# ultra-violet-tooth-sensor-mk-1_0.net
KiCad netlist of a schematic drawn in EAGLE
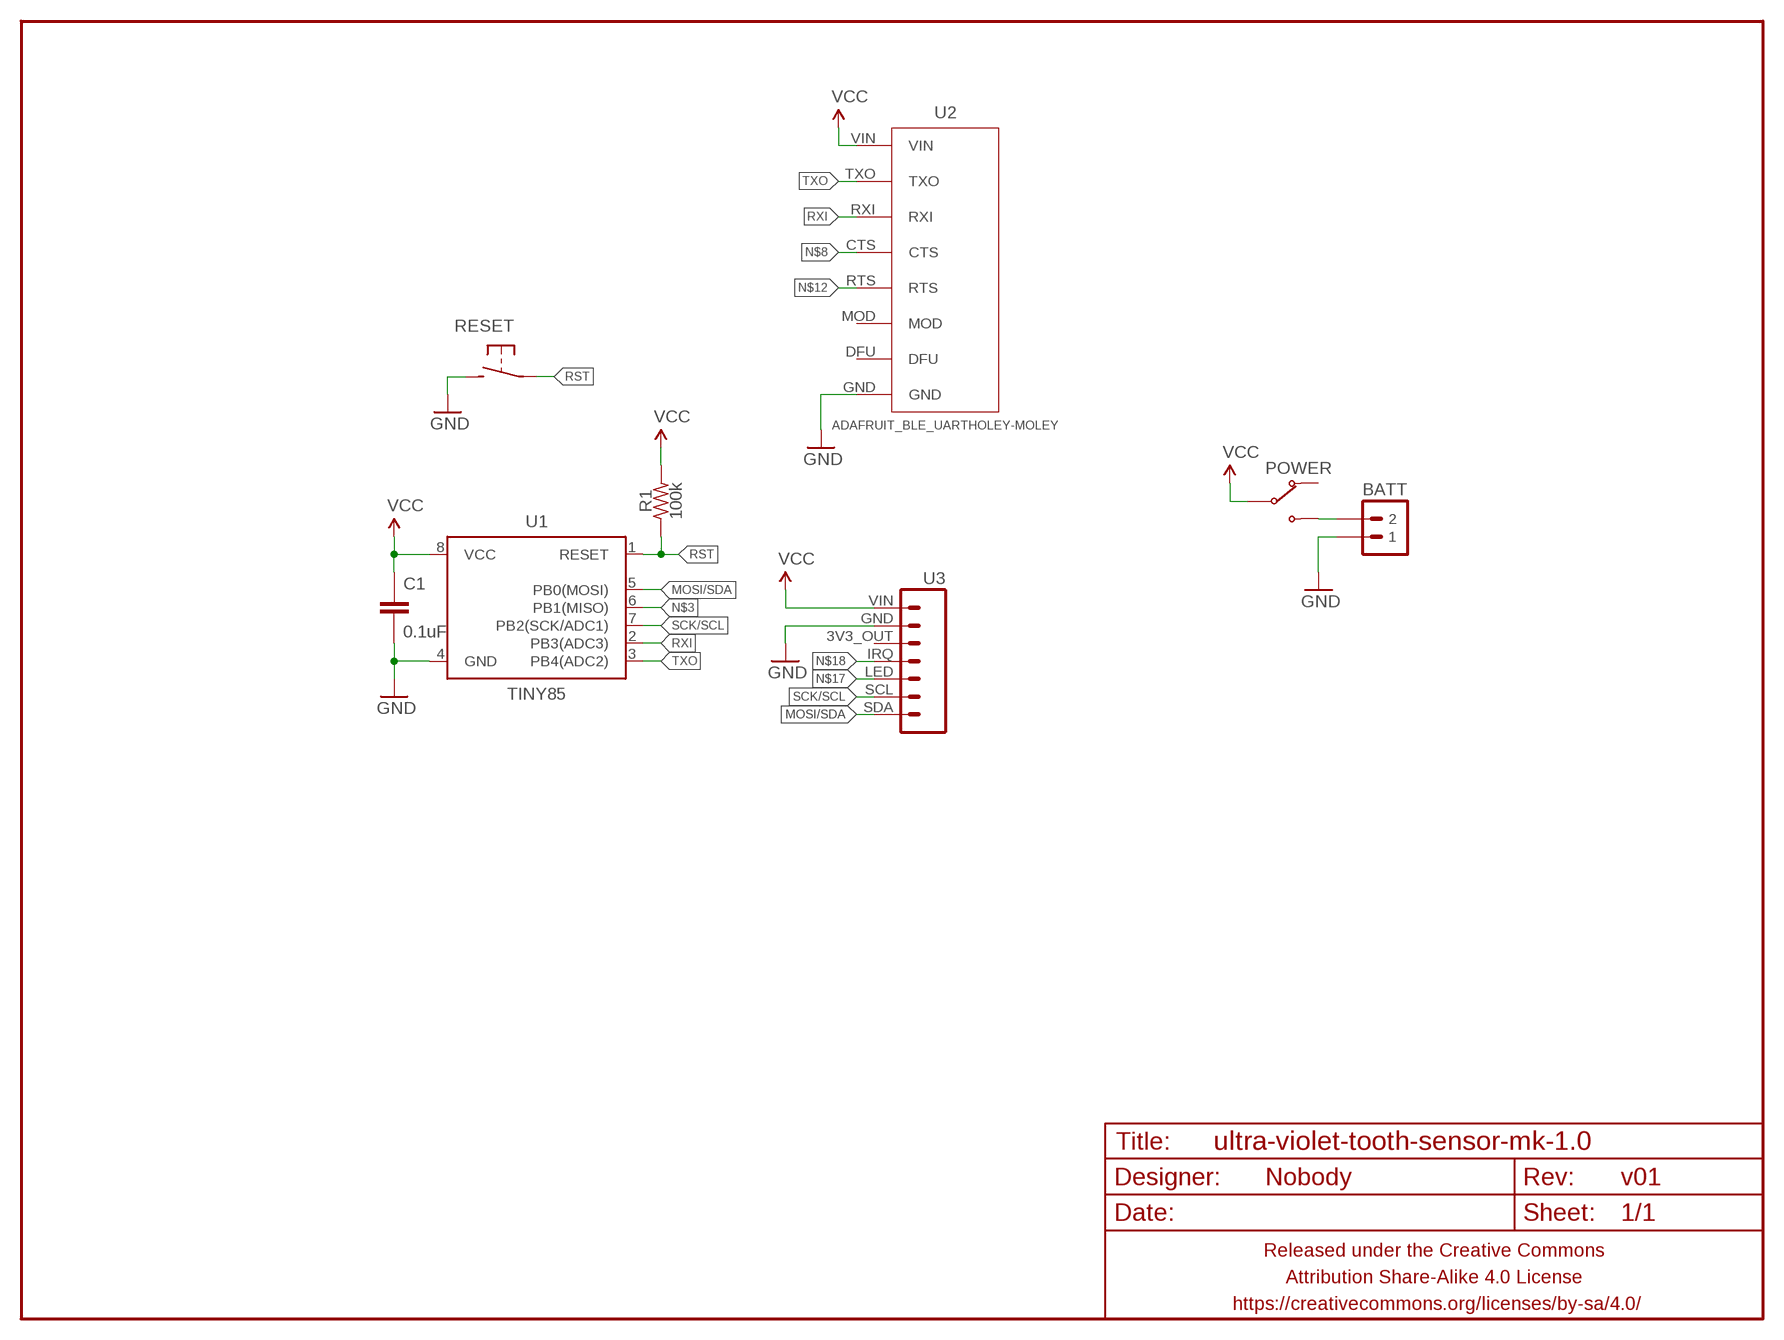
[diagram p0: schematic, sheet 1]

(export (version "E")
  (design (tool "Eeschema 10.0.6"))
  (components
    (comp (ref "BATT")
      (value "M02PTH-CENTERED-R+")
      (footprint "eagle-import:1X02-CENTER-R+")
      (libsource (lib "eagle-import") (part "M02PTH-CENTERED-R+"))
    )
    (comp (ref "C1")
      (value "0.1uF")
      (footprint "eagle-import:C025-024X044")
      (libsource (lib "eagle-import") (part "CAPACITOR-CERAMIC025-024X044"))
    )
    (comp (ref "FRAME1")
      (value "FRAME-LETTERNO_PACKAGE")
      (footprint "eagle-import:DUMMY")
      (fields (field (name "DESIGNER") "Nobody"))
      (libsource (lib "eagle-import") (part "FRAME-LETTERNO_PACKAGE"))
    )
    (comp (ref "POWER")
      (value "SWITCH-SPDTPTH-RA-2.54MM")
      (footprint "eagle-import:SPDT-RA-2.54MM")
      (libsource (lib "eagle-import") (part "SWITCH-SPDTPTH-RA-2.54MM"))
    )
    (comp (ref "R1")
      (value "100k")
      (footprint "eagle-import:RESISTOR-AXIAL-PTH-7.62MM")
      (libsource (lib "eagle-import") (part "RESISTORPTH-AXIAL-7.62MM"))
    )
    (comp (ref "RESET")
      (value "SPST-NO-TACT3MM-RA")
      (footprint "eagle-import:TACTILE-PTH-SIDE")
      (libsource (lib "eagle-import") (part "SPST-NO-TACT3MM-RA"))
    )
    (comp (ref "U1")
      (value "TINY85")
      (footprint "eagle-import:DIP08")
      (libsource (lib "eagle-import") (part "ATTINY45TINY85-20-DIP"))
    )
    (comp (ref "U2")
      (value "ADAFRUIT_BLE_UARTHOLEY-MOLEY")
      (footprint "eagle-import:ADAFRUIT_BLE_UART_HOLEY")
      (libsource (lib "eagle-import") (part "ADAFRUIT_BLE_UARTHOLEY-MOLEY"))
    )
    (comp (ref "U3")
      (value "ADAFRUIT-SI1145-BREAKOUT")
      (footprint "eagle-import:ADAFRUIT-SI1145-BREAKOUT")
      (libsource (lib "eagle-import") (part "ADAFRUIT-SI1145-BREAKOUT"))
    )
  )
  (nets
    (net (code "1") (name "GND") (class "Default")
      (node (ref "BATT") (pin "1") (pinfunction "1_1") (pintype "passive"))
      (node (ref "C1") (pin "2") (pinfunction "2_2") (pintype "passive"))
      (node (ref "RESET") (pin "2") (pinfunction "2_2") (pintype "passive"))
      (node (ref "U1") (pin "4") (pinfunction "GND_4") (pintype "bidirectional"))
      (node (ref "U2") (pin "GND") (pinfunction "GND_GND") (pintype "bidirectional"))
      (node (ref "U3") (pin "GND") (pinfunction "GND_GND") (pintype "passive"))
    )
    (net (code "2") (name "MOSI{slash}SDA") (class "Default")
      (node (ref "U1") (pin "5") (pinfunction "PB0(MOSI)_5") (pintype "bidirectional"))
      (node (ref "U3") (pin "SDA") (pinfunction "SDA_SDA") (pintype "passive"))
    )
    (net (code "3") (name "N$3") (class "Default")
      (node (ref "U1") (pin "6") (pinfunction "PB1(MISO)_6") (pintype "bidirectional"))
    )
    (net (code "4") (name "N$8") (class "Default")
      (node (ref "U2") (pin "CTS") (pinfunction "CTS_CTS") (pintype "bidirectional"))
    )
    (net (code "5") (name "N$12") (class "Default")
      (node (ref "U2") (pin "RTS") (pinfunction "RTS_RTS") (pintype "bidirectional"))
    )
    (net (code "6") (name "N$17") (class "Default")
      (node (ref "U3") (pin "LED") (pinfunction "LED_LED") (pintype "passive"))
    )
    (net (code "7") (name "N$18") (class "Default")
      (node (ref "U3") (pin "IRQ") (pinfunction "IRQ_IRQ") (pintype "passive"))
    )
    (net (code "8") (name "Net-(POWER-NO)") (class "Default")
      (node (ref "BATT") (pin "2") (pinfunction "2_2") (pintype "passive"))
      (node (ref "POWER") (pin "3") (pinfunction "NO_3") (pintype "passive"))
    )
    (net (code "9") (name "RST") (class "Default")
      (node (ref "R1") (pin "P$1") (pinfunction "1_P$1") (pintype "passive"))
      (node (ref "RESET") (pin "1") (pinfunction "1_1") (pintype "passive"))
      (node (ref "U1") (pin "1") (pinfunction "RESET_1") (pintype "bidirectional"))
    )
    (net (code "10") (name "RXI") (class "Default")
      (node (ref "U1") (pin "2") (pinfunction "PB3(ADC3)_2") (pintype "bidirectional"))
      (node (ref "U2") (pin "RXI") (pinfunction "RXI_RXI") (pintype "bidirectional"))
    )
    (net (code "11") (name "SCK{slash}SCL") (class "Default")
      (node (ref "U1") (pin "7") (pinfunction "PB2(SCK/ADC1)_7") (pintype "bidirectional"))
      (node (ref "U3") (pin "SCL") (pinfunction "SCL_SCL") (pintype "passive"))
    )
    (net (code "12") (name "TXO") (class "Default")
      (node (ref "U1") (pin "3") (pinfunction "PB4(ADC2)_3") (pintype "bidirectional"))
      (node (ref "U2") (pin "TXO") (pinfunction "TXO_TXO") (pintype "bidirectional"))
    )
    (net (code "13") (name "VCC") (class "Default")
      (node (ref "C1") (pin "1") (pinfunction "1_1") (pintype "passive"))
      (node (ref "POWER") (pin "2") (pinfunction "COM_2") (pintype "passive"))
      (node (ref "R1") (pin "P$2") (pinfunction "2_P$2") (pintype "passive"))
      (node (ref "U1") (pin "8") (pinfunction "VCC_8") (pintype "bidirectional"))
      (node (ref "U2") (pin "VIN") (pinfunction "VIN_VIN") (pintype "bidirectional"))
      (node (ref "U3") (pin "VIN") (pinfunction "VIN_VIN") (pintype "passive"))
    )
    (net (code "14") (name "unconnected-(POWER-NC-Pad1)") (class "Default")
      (node (ref "POWER") (pin "1") (pinfunction "NC_1") (pintype "passive"))
    )
    (net (code "15") (name "unconnected-(U2-PadDFU)") (class "Default")
      (node (ref "U2") (pin "DFU") (pinfunction "DFU_DFU") (pintype "bidirectional"))
    )
    (net (code "16") (name "unconnected-(U2-PadMOD)") (class "Default")
      (node (ref "U2") (pin "MOD") (pinfunction "MOD_MOD") (pintype "bidirectional"))
    )
    (net (code "17") (name "unconnected-(U3-Pad3V3_OUT)") (class "Default")
      (node (ref "U3") (pin "3V3_OUT") (pinfunction "3V3_OUT_3V3_OUT") (pintype "passive"))
    )
  )
)
